# 03-M2_GoldFingers.net
KiCad netlist of a schematic drawn in Altium Designer
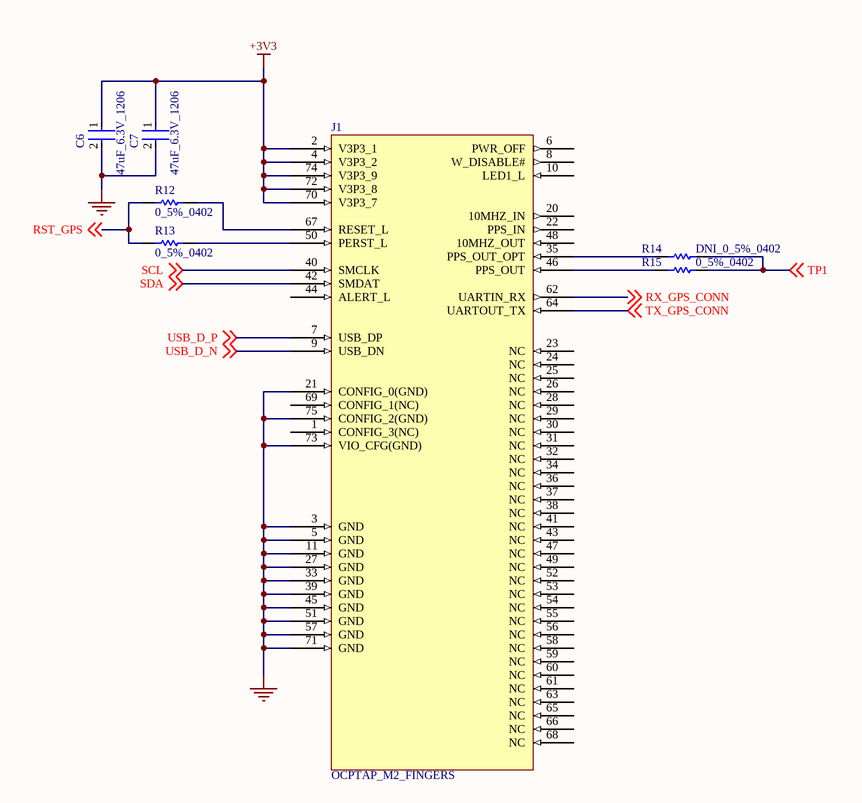
[diagram p0: 03-M2_GoldFingers.SchDoc]

(export (version "E")
  (design (tool "Eeschema 10.0.6"))
  (components
    (comp (ref "C6")
      (value "47uF_6.3V_1206")
      (footprint "FP-GRM31C-0_2-e0_3_0_8-IPC_C")
      (description "Chip Multilayer Ceramic Capacitors for General Purpose, 1206, 47uF, X5R, 15%, 20%, 6.3V")
      (fields (field (name "TOLERANCE") "20%") (field (name "VOLTAGE") "6.3V"))
      (libsource (lib "Altium Content Vault") (part "02cd4be3c70576c341d710602a673aa"))
    )
    (comp (ref "C7")
      (value "47uF_6.3V_1206")
      (footprint "FP-GRM31C-0_2-e0_3_0_8-IPC_C")
      (description "Chip Multilayer Ceramic Capacitors for General Purpose, 1206, 47uF, X5R, 15%, 20%, 6.3V")
      (fields (field (name "TOLERANCE") "20%") (field (name "VOLTAGE") "6.3V"))
      (libsource (lib "Altium Content Vault") (part "02cd4be3c70576c341d710602a673aa"))
    )
    (comp (ref "J1")
      (value "OCPTAP_M2_FINGERS")
      (footprint "OCPTAP M2 FINGERS")
      (libsource (lib "M2_Library") (part "OCPTAP_M2_FINGERS"))
    )
    (comp (ref "R12")
      (value "0_5%_0402")
      (footprint "RESC1005X40X25NL05T10")
      (fields (field (name "MANUFACTURER") "Panasonic") (field (name "PART NUMBER") "ERJ-U020R00X"))
      (libsource (lib "Altium Content Vault") (part "RES"))
    )
    (comp (ref "R13")
      (value "0_5%_0402")
      (footprint "RESC1005X40X25NL05T10")
      (fields (field (name "MANUFACTURER") "Panasonic") (field (name "PART NUMBER") "ERJ-U020R00X"))
      (libsource (lib "Altium Content Vault") (part "RES"))
    )
    (comp (ref "R14")
      (value "DNI_0_5%_0402")
      (footprint "RESC1005X40X25NL05T10")
      (fields (field (name "MANUFACTURER") "Panasonic") (field (name "PART NUMBER") "ERJ-U020R00X"))
      (libsource (lib "Altium Content Vault") (part "RES"))
    )
    (comp (ref "R15")
      (value "0_5%_0402")
      (footprint "RESC1005X40X25NL05T10")
      (fields (field (name "MANUFACTURER") "Panasonic") (field (name "PART NUMBER") "ERJ-U020R00X"))
      (libsource (lib "Altium Content Vault") (part "RES"))
    )
  )
  (nets
    (net (code "1") (name "+3V3") (class "Default")
      (node (ref "C6") (pin "1") (pinfunction "1_1") (pintype "passive"))
      (node (ref "C7") (pin "1") (pinfunction "1_1") (pintype "passive"))
      (node (ref "J1") (pin "2") (pinfunction "V3P3_1_2") (pintype "input"))
      (node (ref "J1") (pin "4") (pinfunction "V3P3_2_4") (pintype "input"))
      (node (ref "J1") (pin "70") (pinfunction "V3P3_7_70") (pintype "input"))
      (node (ref "J1") (pin "72") (pinfunction "V3P3_8_72") (pintype "input"))
      (node (ref "J1") (pin "74") (pinfunction "V3P3_9_74") (pintype "input"))
    )
    (net (code "2") (name "GND") (class "Default")
      (node (ref "C6") (pin "2") (pinfunction "2_2") (pintype "passive"))
      (node (ref "C7") (pin "2") (pinfunction "2_2") (pintype "passive"))
      (node (ref "J1") (pin "11") (pinfunction "GND_11") (pintype "input"))
      (node (ref "J1") (pin "21") (pinfunction "CONFIG_0(GND)_21") (pintype "input"))
      (node (ref "J1") (pin "27") (pinfunction "GND_27") (pintype "input"))
      (node (ref "J1") (pin "3") (pinfunction "GND_3") (pintype "input"))
      (node (ref "J1") (pin "33") (pinfunction "GND_33") (pintype "input"))
      (node (ref "J1") (pin "39") (pinfunction "GND_39") (pintype "input"))
      (node (ref "J1") (pin "45") (pinfunction "GND_45") (pintype "input"))
      (node (ref "J1") (pin "5") (pinfunction "GND_5") (pintype "input"))
      (node (ref "J1") (pin "51") (pinfunction "GND_51") (pintype "input"))
      (node (ref "J1") (pin "57") (pinfunction "GND_57") (pintype "input"))
      (node (ref "J1") (pin "71") (pinfunction "GND_71") (pintype "input"))
      (node (ref "J1") (pin "73") (pinfunction "VIO_CFG(GND)_73") (pintype "input"))
      (node (ref "J1") (pin "75") (pinfunction "CONFIG_2(GND)_75") (pintype "input"))
    )
    (net (code "3") (name "Net-(J1-PERST_L)") (class "Default")
      (node (ref "J1") (pin "50") (pinfunction "PERST_L_50") (pintype "input"))
      (node (ref "R13") (pin "2") (pinfunction "2_2") (pintype "passive"))
    )
    (net (code "4") (name "Net-(J1-PPS_OUT)") (class "Default")
      (node (ref "J1") (pin "46") (pinfunction "PPS_OUT_46") (pintype "input"))
      (node (ref "R15") (pin "1") (pinfunction "1_1") (pintype "passive"))
    )
    (net (code "5") (name "Net-(J1-PPS_OUT_OPT)") (class "Default")
      (node (ref "J1") (pin "35") (pinfunction "PPS_OUT_OPT_35") (pintype "input"))
      (node (ref "R14") (pin "1") (pinfunction "1_1") (pintype "passive"))
    )
    (net (code "6") (name "Net-(J1-RESET_L)") (class "Default")
      (node (ref "J1") (pin "67") (pinfunction "RESET_L_67") (pintype "input"))
      (node (ref "R12") (pin "2") (pinfunction "2_2") (pintype "passive"))
    )
    (net (code "7") (name "RST_GPS") (class "Default")
      (node (ref "R12") (pin "1") (pinfunction "1_1") (pintype "passive"))
      (node (ref "R13") (pin "1") (pinfunction "1_1") (pintype "passive"))
    )
    (net (code "8") (name "RX_GPS_CONN") (class "Default")
      (node (ref "J1") (pin "62") (pinfunction "UARTIN_RX_62") (pintype "output"))
    )
    (net (code "9") (name "SCL") (class "Default")
      (node (ref "J1") (pin "40") (pinfunction "SMCLK_40") (pintype "input"))
    )
    (net (code "10") (name "SDA") (class "Default")
      (node (ref "J1") (pin "42") (pinfunction "SMDAT_42") (pintype "input"))
    )
    (net (code "11") (name "TP1") (class "Default")
      (node (ref "R14") (pin "2") (pinfunction "2_2") (pintype "passive"))
      (node (ref "R15") (pin "2") (pinfunction "2_2") (pintype "passive"))
    )
    (net (code "12") (name "TX_GPS_CONN") (class "Default")
      (node (ref "J1") (pin "64") (pinfunction "UARTOUT_TX_64") (pintype "input"))
    )
    (net (code "13") (name "USB_D_N") (class "Default")
      (node (ref "J1") (pin "9") (pinfunction "USB_DN_9") (pintype "input"))
    )
    (net (code "14") (name "USB_D_P") (class "Default")
      (node (ref "J1") (pin "7") (pinfunction "USB_DP_7") (pintype "input"))
    )
    (net (code "15") (name "unconnected-(J1-10MHZ_IN-Pad20)") (class "Default")
      (node (ref "J1") (pin "20") (pinfunction "10MHZ_IN_20") (pintype "output"))
    )
    (net (code "16") (name "unconnected-(J1-10MHZ_OUT-Pad48)") (class "Default")
      (node (ref "J1") (pin "48") (pinfunction "10MHZ_OUT_48") (pintype "input"))
    )
    (net (code "17") (name "unconnected-(J1-ALERT_L-Pad44)") (class "Default")
      (node (ref "J1") (pin "44") (pinfunction "ALERT_L_44") (pintype "input"))
    )
    (net (code "18") (name "unconnected-(J1-CONFIG_1(NC)-Pad69)") (class "Default")
      (node (ref "J1") (pin "69") (pinfunction "CONFIG_1(NC)_69") (pintype "input"))
    )
    (net (code "19") (name "unconnected-(J1-CONFIG_3(NC)-Pad1)") (class "Default")
      (node (ref "J1") (pin "1") (pinfunction "CONFIG_3(NC)_1") (pintype "input"))
    )
    (net (code "20") (name "unconnected-(J1-LED1_L-Pad10)") (class "Default")
      (node (ref "J1") (pin "10") (pinfunction "LED1_L_10") (pintype "input"))
    )
    (net (code "21") (name "unconnected-(J1-NC-Pad23)") (class "Default")
      (node (ref "J1") (pin "23") (pinfunction "NC_23") (pintype "input"))
    )
    (net (code "22") (name "unconnected-(J1-NC-Pad24)") (class "Default")
      (node (ref "J1") (pin "24") (pinfunction "NC_24") (pintype "input"))
    )
    (net (code "23") (name "unconnected-(J1-NC-Pad25)") (class "Default")
      (node (ref "J1") (pin "25") (pinfunction "NC_25") (pintype "input"))
    )
    (net (code "24") (name "unconnected-(J1-NC-Pad26)") (class "Default")
      (node (ref "J1") (pin "26") (pinfunction "NC_26") (pintype "input"))
    )
    (net (code "25") (name "unconnected-(J1-NC-Pad28)") (class "Default")
      (node (ref "J1") (pin "28") (pinfunction "NC_28") (pintype "input"))
    )
    (net (code "26") (name "unconnected-(J1-NC-Pad29)") (class "Default")
      (node (ref "J1") (pin "29") (pinfunction "NC_29") (pintype "input"))
    )
    (net (code "27") (name "unconnected-(J1-NC-Pad30)") (class "Default")
      (node (ref "J1") (pin "30") (pinfunction "NC_30") (pintype "input"))
    )
    (net (code "28") (name "unconnected-(J1-NC-Pad31)") (class "Default")
      (node (ref "J1") (pin "31") (pinfunction "NC_31") (pintype "input"))
    )
    (net (code "29") (name "unconnected-(J1-NC-Pad32)") (class "Default")
      (node (ref "J1") (pin "32") (pinfunction "NC_32") (pintype "input"))
    )
    (net (code "30") (name "unconnected-(J1-NC-Pad34)") (class "Default")
      (node (ref "J1") (pin "34") (pinfunction "NC_34") (pintype "input"))
    )
    (net (code "31") (name "unconnected-(J1-NC-Pad36)") (class "Default")
      (node (ref "J1") (pin "36") (pinfunction "NC_36") (pintype "input"))
    )
    (net (code "32") (name "unconnected-(J1-NC-Pad37)") (class "Default")
      (node (ref "J1") (pin "37") (pinfunction "NC_37") (pintype "input"))
    )
    (net (code "33") (name "unconnected-(J1-NC-Pad38)") (class "Default")
      (node (ref "J1") (pin "38") (pinfunction "NC_38") (pintype "input"))
    )
    (net (code "34") (name "unconnected-(J1-NC-Pad41)") (class "Default")
      (node (ref "J1") (pin "41") (pinfunction "NC_41") (pintype "input"))
    )
    (net (code "35") (name "unconnected-(J1-NC-Pad43)") (class "Default")
      (node (ref "J1") (pin "43") (pinfunction "NC_43") (pintype "input"))
    )
    (net (code "36") (name "unconnected-(J1-NC-Pad47)") (class "Default")
      (node (ref "J1") (pin "47") (pinfunction "NC_47") (pintype "input"))
    )
    (net (code "37") (name "unconnected-(J1-NC-Pad49)") (class "Default")
      (node (ref "J1") (pin "49") (pinfunction "NC_49") (pintype "input"))
    )
    (net (code "38") (name "unconnected-(J1-NC-Pad52)") (class "Default")
      (node (ref "J1") (pin "52") (pinfunction "NC_52") (pintype "input"))
    )
    (net (code "39") (name "unconnected-(J1-NC-Pad53)") (class "Default")
      (node (ref "J1") (pin "53") (pinfunction "NC_53") (pintype "input"))
    )
    (net (code "40") (name "unconnected-(J1-NC-Pad54)") (class "Default")
      (node (ref "J1") (pin "54") (pinfunction "NC_54") (pintype "input"))
    )
    (net (code "41") (name "unconnected-(J1-NC-Pad55)") (class "Default")
      (node (ref "J1") (pin "55") (pinfunction "NC_55") (pintype "input"))
    )
    (net (code "42") (name "unconnected-(J1-NC-Pad56)") (class "Default")
      (node (ref "J1") (pin "56") (pinfunction "NC_56") (pintype "input"))
    )
    (net (code "43") (name "unconnected-(J1-NC-Pad58)") (class "Default")
      (node (ref "J1") (pin "58") (pinfunction "NC_58") (pintype "input"))
    )
    (net (code "44") (name "unconnected-(J1-NC-Pad59)") (class "Default")
      (node (ref "J1") (pin "59") (pinfunction "NC_59") (pintype "input"))
    )
    (net (code "45") (name "unconnected-(J1-NC-Pad60)") (class "Default")
      (node (ref "J1") (pin "60") (pinfunction "NC_60") (pintype "input"))
    )
    (net (code "46") (name "unconnected-(J1-NC-Pad61)") (class "Default")
      (node (ref "J1") (pin "61") (pinfunction "NC_61") (pintype "input"))
    )
    (net (code "47") (name "unconnected-(J1-NC-Pad63)") (class "Default")
      (node (ref "J1") (pin "63") (pinfunction "NC_63") (pintype "input"))
    )
    (net (code "48") (name "unconnected-(J1-NC-Pad65)") (class "Default")
      (node (ref "J1") (pin "65") (pinfunction "NC_65") (pintype "input"))
    )
    (net (code "49") (name "unconnected-(J1-NC-Pad66)") (class "Default")
      (node (ref "J1") (pin "66") (pinfunction "NC_66") (pintype "input"))
    )
    (net (code "50") (name "unconnected-(J1-NC-Pad68)") (class "Default")
      (node (ref "J1") (pin "68") (pinfunction "NC_68") (pintype "input"))
    )
    (net (code "51") (name "unconnected-(J1-PPS_IN-Pad22)") (class "Default")
      (node (ref "J1") (pin "22") (pinfunction "PPS_IN_22") (pintype "output"))
    )
    (net (code "52") (name "unconnected-(J1-PWR_OFF-Pad6)") (class "Default")
      (node (ref "J1") (pin "6") (pinfunction "PWR_OFF_6") (pintype "output"))
    )
    (net (code "53") (name "unconnected-(J1-W_DISABLE#-Pad8)") (class "Default")
      (node (ref "J1") (pin "8") (pinfunction "W_DISABLE#_8") (pintype "output"))
    )
  )
)
